# LC_LightCanvas_Rev_1.net
KiCad netlist of a schematic drawn in EAGLE
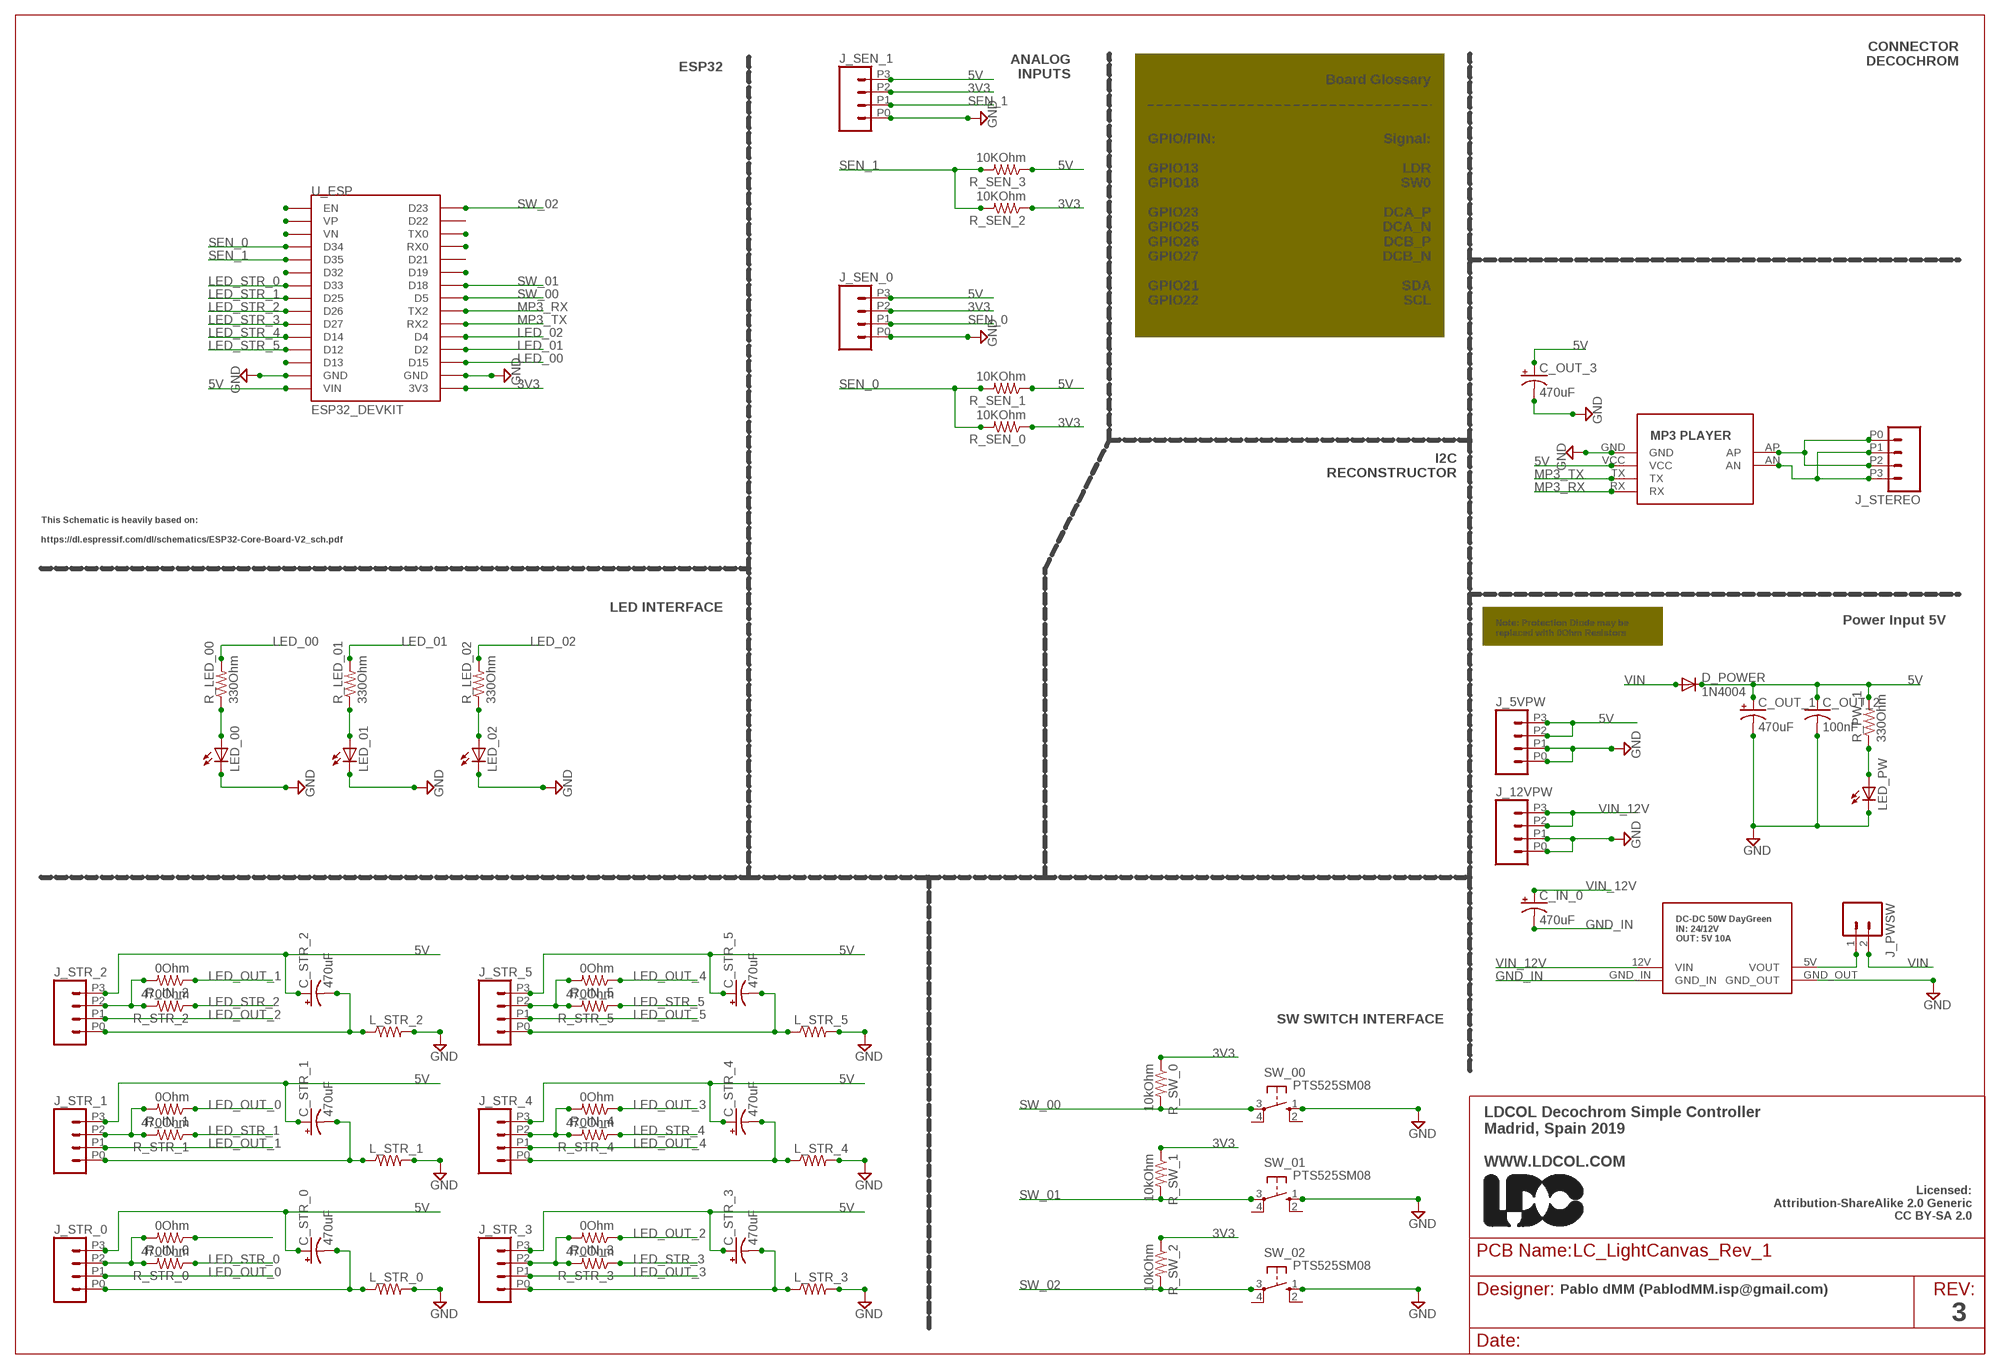
[diagram p0: schematic, sheet 1]

(export (version "E")
  (design (tool "Eeschema 10.0.6"))
  (components
    (comp (ref "C_IN_0")
      (value "470uF")
      (footprint "eagle-import:E5-10,5")
      (libsource (lib "eagle-import") (part "CPOL-USE5-10.5"))
    )
    (comp (ref "C_OUT_1")
      (value "470uF")
      (footprint "eagle-import:E5-10,5")
      (libsource (lib "eagle-import") (part "CPOL-USE5-10.5"))
    )
    (comp (ref "C_OUT_2")
      (value "100nF")
      (footprint "eagle-import:C0805")
      (libsource (lib "eagle-import") (part "C-USC0805"))
    )
    (comp (ref "C_OUT_3")
      (value "470uF")
      (footprint "eagle-import:E5-10,5")
      (libsource (lib "eagle-import") (part "CPOL-USE5-10.5"))
    )
    (comp (ref "C_STR_0")
      (value "470uF")
      (footprint "eagle-import:E5-10,5")
      (libsource (lib "eagle-import") (part "CPOL-USE5-10.5"))
    )
    (comp (ref "C_STR_1")
      (value "470uF")
      (footprint "eagle-import:E5-10,5")
      (libsource (lib "eagle-import") (part "CPOL-USE5-10.5"))
    )
    (comp (ref "C_STR_2")
      (value "470uF")
      (footprint "eagle-import:E5-10,5")
      (libsource (lib "eagle-import") (part "CPOL-USE5-10.5"))
    )
    (comp (ref "C_STR_3")
      (value "470uF")
      (footprint "eagle-import:E5-10,5")
      (libsource (lib "eagle-import") (part "CPOL-USE5-10.5"))
    )
    (comp (ref "C_STR_4")
      (value "470uF")
      (footprint "eagle-import:E5-10,5")
      (libsource (lib "eagle-import") (part "CPOL-USE5-10.5"))
    )
    (comp (ref "C_STR_5")
      (value "470uF")
      (footprint "eagle-import:E5-10,5")
      (libsource (lib "eagle-import") (part "CPOL-USE5-10.5"))
    )
    (comp (ref "D_POWER")
      (value "1N4004")
      (footprint "eagle-import:DO41-10")
      (libsource (lib "eagle-import") (part "1N4004"))
    )
    (comp (ref "J_5VPW")
      (value "M04")
      (footprint "eagle-import:1X04_2.54_SCREWTERM")
      (libsource (lib "eagle-import") (part "M04"))
    )
    (comp (ref "J_12VPW")
      (value "M04")
      (footprint "eagle-import:1X04_2.54_SCREWTERM")
      (libsource (lib "eagle-import") (part "M04"))
    )
    (comp (ref "J_PWSW")
      (value "M023.5MM-NO_SILK")
      (footprint "eagle-import:SCREWTERMINAL-3.5MM-2-NS")
      (libsource (lib "eagle-import") (part "M023.5MM-NO_SILK"))
    )
    (comp (ref "J_SEN_0")
      (value "M04")
      (footprint "eagle-import:1X04_2.54_SCREWTERM")
      (libsource (lib "eagle-import") (part "M04"))
    )
    (comp (ref "J_SEN_1")
      (value "M04")
      (footprint "eagle-import:1X04_2.54_SCREWTERM")
      (libsource (lib "eagle-import") (part "M04"))
    )
    (comp (ref "J_STEREO")
      (value "M04")
      (footprint "eagle-import:1X04_2.54_SCREWTERM")
      (libsource (lib "eagle-import") (part "M04"))
    )
    (comp (ref "J_STR_0")
      (value "M04")
      (footprint "eagle-import:1X04_2.54_SCREWTERM")
      (libsource (lib "eagle-import") (part "M04"))
    )
    (comp (ref "J_STR_1")
      (value "M04")
      (footprint "eagle-import:1X04_2.54_SCREWTERM")
      (libsource (lib "eagle-import") (part "M04"))
    )
    (comp (ref "J_STR_2")
      (value "M04")
      (footprint "eagle-import:1X04_2.54_SCREWTERM")
      (libsource (lib "eagle-import") (part "M04"))
    )
    (comp (ref "J_STR_3")
      (value "M04")
      (footprint "eagle-import:1X04_2.54_SCREWTERM")
      (libsource (lib "eagle-import") (part "M04"))
    )
    (comp (ref "J_STR_4")
      (value "M04")
      (footprint "eagle-import:1X04_2.54_SCREWTERM")
      (libsource (lib "eagle-import") (part "M04"))
    )
    (comp (ref "J_STR_5")
      (value "M04")
      (footprint "eagle-import:1X04_2.54_SCREWTERM")
      (libsource (lib "eagle-import") (part "M04"))
    )
    (comp (ref "LED_00")
      (value "LEDCHIPLED_0805")
      (footprint "eagle-import:CHIPLED_0805")
      (libsource (lib "eagle-import") (part "LEDCHIPLED_0805"))
    )
    (comp (ref "LED_01")
      (value "LEDCHIPLED_0805")
      (footprint "eagle-import:CHIPLED_0805")
      (libsource (lib "eagle-import") (part "LEDCHIPLED_0805"))
    )
    (comp (ref "LED_02")
      (value "LEDCHIPLED_0805")
      (footprint "eagle-import:CHIPLED_0805")
      (libsource (lib "eagle-import") (part "LEDCHIPLED_0805"))
    )
    (comp (ref "LED_PW")
      (value "LEDCHIPLED_0805")
      (footprint "eagle-import:CHIPLED_0805")
      (libsource (lib "eagle-import") (part "LEDCHIPLED_0805"))
    )
    (comp (ref "L_STR_0")
      (value "R-US_R2012")
      (footprint "eagle-import:R2012")
      (libsource (lib "eagle-import") (part "R-US_R2012"))
    )
    (comp (ref "L_STR_1")
      (value "R-US_R2012")
      (footprint "eagle-import:R2012")
      (libsource (lib "eagle-import") (part "R-US_R2012"))
    )
    (comp (ref "L_STR_2")
      (value "R-US_R2012")
      (footprint "eagle-import:R2012")
      (libsource (lib "eagle-import") (part "R-US_R2012"))
    )
    (comp (ref "L_STR_3")
      (value "R-US_R2012")
      (footprint "eagle-import:R2012")
      (libsource (lib "eagle-import") (part "R-US_R2012"))
    )
    (comp (ref "L_STR_4")
      (value "R-US_R2012")
      (footprint "eagle-import:R2012")
      (libsource (lib "eagle-import") (part "R-US_R2012"))
    )
    (comp (ref "L_STR_5")
      (value "R-US_R2012")
      (footprint "eagle-import:R2012")
      (libsource (lib "eagle-import") (part "R-US_R2012"))
    )
    (comp (ref "R_IN_0")
      (value "0Ohm")
      (footprint "eagle-import:M0805")
      (libsource (lib "eagle-import") (part "R-US_M0805"))
    )
    (comp (ref "R_IN_1")
      (value "0Ohm")
      (footprint "eagle-import:M0805")
      (libsource (lib "eagle-import") (part "R-US_M0805"))
    )
    (comp (ref "R_IN_2")
      (value "0Ohm")
      (footprint "eagle-import:M0805")
      (libsource (lib "eagle-import") (part "R-US_M0805"))
    )
    (comp (ref "R_IN_3")
      (value "0Ohm")
      (footprint "eagle-import:M0805")
      (libsource (lib "eagle-import") (part "R-US_M0805"))
    )
    (comp (ref "R_IN_4")
      (value "0Ohm")
      (footprint "eagle-import:M0805")
      (libsource (lib "eagle-import") (part "R-US_M0805"))
    )
    (comp (ref "R_IN_5")
      (value "0Ohm")
      (footprint "eagle-import:M0805")
      (libsource (lib "eagle-import") (part "R-US_M0805"))
    )
    (comp (ref "R_LED_00")
      (value "330Ohm")
      (footprint "eagle-import:M0805")
      (libsource (lib "eagle-import") (part "R-US_M0805"))
    )
    (comp (ref "R_LED_01")
      (value "330Ohm")
      (footprint "eagle-import:M0805")
      (libsource (lib "eagle-import") (part "R-US_M0805"))
    )
    (comp (ref "R_LED_02")
      (value "330Ohm")
      (footprint "eagle-import:M0805")
      (libsource (lib "eagle-import") (part "R-US_M0805"))
    )
    (comp (ref "R_PW_1")
      (value "330Ohm")
      (footprint "eagle-import:M0805")
      (libsource (lib "eagle-import") (part "R-US_M0805"))
    )
    (comp (ref "R_SEN_0")
      (value "10KOhm")
      (footprint "eagle-import:M1206")
      (libsource (lib "eagle-import") (part "R-US_M1206"))
    )
    (comp (ref "R_SEN_1")
      (value "10KOhm")
      (footprint "eagle-import:M1206")
      (libsource (lib "eagle-import") (part "R-US_M1206"))
    )
    (comp (ref "R_SEN_2")
      (value "10KOhm")
      (footprint "eagle-import:M1206")
      (libsource (lib "eagle-import") (part "R-US_M1206"))
    )
    (comp (ref "R_SEN_3")
      (value "10KOhm")
      (footprint "eagle-import:M1206")
      (libsource (lib "eagle-import") (part "R-US_M1206"))
    )
    (comp (ref "R_STR_0")
      (value "470Ohm")
      (footprint "eagle-import:M0805")
      (libsource (lib "eagle-import") (part "R-US_M0805"))
    )
    (comp (ref "R_STR_1")
      (value "470Ohm")
      (footprint "eagle-import:M0805")
      (libsource (lib "eagle-import") (part "R-US_M0805"))
    )
    (comp (ref "R_STR_2")
      (value "470Ohm")
      (footprint "eagle-import:M0805")
      (libsource (lib "eagle-import") (part "R-US_M0805"))
    )
    (comp (ref "R_STR_3")
      (value "470Ohm")
      (footprint "eagle-import:M0805")
      (libsource (lib "eagle-import") (part "R-US_M0805"))
    )
    (comp (ref "R_STR_4")
      (value "470Ohm")
      (footprint "eagle-import:M0805")
      (libsource (lib "eagle-import") (part "R-US_M0805"))
    )
    (comp (ref "R_STR_5")
      (value "470Ohm")
      (footprint "eagle-import:M0805")
      (libsource (lib "eagle-import") (part "R-US_M0805"))
    )
    (comp (ref "R_SW_0")
      (value "10kOhm")
      (footprint "eagle-import:M0805")
      (libsource (lib "eagle-import") (part "R-US_M0805"))
    )
    (comp (ref "R_SW_1")
      (value "10kOhm")
      (footprint "eagle-import:M0805")
      (libsource (lib "eagle-import") (part "R-US_M0805"))
    )
    (comp (ref "R_SW_2")
      (value "10kOhm")
      (footprint "eagle-import:M0805")
      (libsource (lib "eagle-import") (part "R-US_M0805"))
    )
    (comp (ref "SW_00")
      (value "PTS525SM08")
      (footprint "eagle-import:SM08")
      (fields (field (name "MF") "C&K Components") (field (name "MPN") "PTS525SM08SMTR2LFS"))
      (libsource (lib "eagle-import") (part "PTS52508SM"))
    )
    (comp (ref "SW_01")
      (value "PTS525SM08")
      (footprint "eagle-import:SM08")
      (fields (field (name "MF") "C&K Components") (field (name "MPN") "PTS525SM08SMTR2LFS"))
      (libsource (lib "eagle-import") (part "PTS52508SM"))
    )
    (comp (ref "SW_02")
      (value "PTS525SM08")
      (footprint "eagle-import:SM08")
      (fields (field (name "MF") "C&K Components") (field (name "MPN") "PTS525SM08SMTR2LFS"))
      (libsource (lib "eagle-import") (part "PTS52508SM"))
    )
    (comp (ref "U$1")
      (value "DC_CONVERTER")
      (footprint "eagle-import:DC_CONVERTER")
      (libsource (lib "eagle-import") (part "DC_CONVERTER"))
    )
    (comp (ref "U$2")
      (value "MP3_PLAYER")
      (footprint "eagle-import:MP3_PLAYER")
      (libsource (lib "eagle-import") (part "MP3_PLAYER"))
    )
    (comp (ref "U_ESP")
      (value "ESP32_DEVKIT")
      (footprint "eagle-import:ESP32_DEVKIT")
      (libsource (lib "eagle-import") (part "ESP32_DEVKIT"))
    )
  )
  (nets
    (net (code "1") (name "/3V3") (class "Default")
      (node (ref "J_SEN_0") (pin "P2") (pinfunction "3_P2") (pintype "passive"))
      (node (ref "J_SEN_1") (pin "P2") (pinfunction "3_P2") (pintype "passive"))
      (node (ref "R_SEN_0") (pin "1") (pinfunction "1_1") (pintype "passive"))
      (node (ref "R_SEN_2") (pin "1") (pinfunction "1_1") (pintype "passive"))
      (node (ref "R_SW_0") (pin "1") (pinfunction "1_1") (pintype "passive"))
      (node (ref "R_SW_1") (pin "1") (pinfunction "1_1") (pintype "passive"))
      (node (ref "R_SW_2") (pin "1") (pinfunction "1_1") (pintype "passive"))
      (node (ref "U_ESP") (pin "3V3") (pinfunction "3V3_3V3") (pintype "bidirectional"))
    )
    (net (code "2") (name "/5V") (class "Default")
      (node (ref "C_OUT_1") (pin "+") (pinfunction "+_+") (pintype "passive"))
      (node (ref "C_OUT_2") (pin "1") (pinfunction "1_1") (pintype "passive"))
      (node (ref "C_OUT_3") (pin "+") (pinfunction "+_+") (pintype "passive"))
      (node (ref "C_STR_0") (pin "+") (pinfunction "+_+") (pintype "passive"))
      (node (ref "C_STR_1") (pin "+") (pinfunction "+_+") (pintype "passive"))
      (node (ref "C_STR_2") (pin "+") (pinfunction "+_+") (pintype "passive"))
      (node (ref "C_STR_3") (pin "+") (pinfunction "+_+") (pintype "passive"))
      (node (ref "C_STR_4") (pin "+") (pinfunction "+_+") (pintype "passive"))
      (node (ref "C_STR_5") (pin "+") (pinfunction "+_+") (pintype "passive"))
      (node (ref "D_POWER") (pin "C") (pinfunction "C_C") (pintype "passive"))
      (node (ref "J_5VPW") (pin "P2") (pinfunction "3_P2") (pintype "passive"))
      (node (ref "J_5VPW") (pin "P3") (pinfunction "4_P3") (pintype "passive"))
      (node (ref "J_SEN_0") (pin "P3") (pinfunction "4_P3") (pintype "passive"))
      (node (ref "J_SEN_1") (pin "P3") (pinfunction "4_P3") (pintype "passive"))
      (node (ref "J_STR_0") (pin "P3") (pinfunction "4_P3") (pintype "passive"))
      (node (ref "J_STR_1") (pin "P3") (pinfunction "4_P3") (pintype "passive"))
      (node (ref "J_STR_2") (pin "P3") (pinfunction "4_P3") (pintype "passive"))
      (node (ref "J_STR_3") (pin "P3") (pinfunction "4_P3") (pintype "passive"))
      (node (ref "J_STR_4") (pin "P3") (pinfunction "4_P3") (pintype "passive"))
      (node (ref "J_STR_5") (pin "P3") (pinfunction "4_P3") (pintype "passive"))
      (node (ref "R_PW_1") (pin "2") (pinfunction "2_2") (pintype "passive"))
      (node (ref "R_SEN_1") (pin "1") (pinfunction "1_1") (pintype "passive"))
      (node (ref "R_SEN_3") (pin "1") (pinfunction "1_1") (pintype "passive"))
      (node (ref "U$2") (pin "VCC") (pinfunction "VCC_VCC") (pintype "bidirectional"))
      (node (ref "U_ESP") (pin "VIN") (pinfunction "VIN_VIN") (pintype "bidirectional"))
    )
    (net (code "3") (name "/GND_IN") (class "Default")
      (node (ref "C_IN_0") (pin "-") (pinfunction "-_-") (pintype "passive"))
      (node (ref "U$1") (pin "GND_IN") (pinfunction "GND_IN_GND_IN") (pintype "bidirectional"))
    )
    (net (code "4") (name "/LED_00") (class "Default")
      (node (ref "R_LED_00") (pin "2") (pinfunction "2_2") (pintype "passive"))
      (node (ref "U_ESP") (pin "D15") (pinfunction "D15_D15") (pintype "bidirectional"))
    )
    (net (code "5") (name "/LED_01") (class "Default")
      (node (ref "R_LED_01") (pin "2") (pinfunction "2_2") (pintype "passive"))
      (node (ref "U_ESP") (pin "D2") (pinfunction "D2_D2") (pintype "bidirectional"))
    )
    (net (code "6") (name "/LED_02") (class "Default")
      (node (ref "R_LED_02") (pin "2") (pinfunction "2_2") (pintype "passive"))
      (node (ref "U_ESP") (pin "D4") (pinfunction "D4_D4") (pintype "bidirectional"))
    )
    (net (code "7") (name "/LED_OUT_0") (class "Default")
      (node (ref "J_STR_0") (pin "P1") (pinfunction "2_P1") (pintype "passive"))
      (node (ref "R_IN_1") (pin "1") (pinfunction "1_1") (pintype "passive"))
    )
    (net (code "8") (name "/LED_OUT_1") (class "Default")
      (node (ref "J_STR_1") (pin "P1") (pinfunction "2_P1") (pintype "passive"))
      (node (ref "R_IN_2") (pin "1") (pinfunction "1_1") (pintype "passive"))
    )
    (net (code "9") (name "/LED_OUT_2") (class "Default")
      (node (ref "J_STR_2") (pin "P1") (pinfunction "2_P1") (pintype "passive"))
      (node (ref "R_IN_3") (pin "1") (pinfunction "1_1") (pintype "passive"))
    )
    (net (code "10") (name "/LED_OUT_3") (class "Default")
      (node (ref "J_STR_3") (pin "P1") (pinfunction "2_P1") (pintype "passive"))
      (node (ref "R_IN_4") (pin "1") (pinfunction "1_1") (pintype "passive"))
    )
    (net (code "11") (name "/LED_OUT_4") (class "Default")
      (node (ref "J_STR_4") (pin "P1") (pinfunction "2_P1") (pintype "passive"))
      (node (ref "R_IN_5") (pin "1") (pinfunction "1_1") (pintype "passive"))
    )
    (net (code "12") (name "/LED_OUT_5") (class "Default")
      (node (ref "J_STR_5") (pin "P1") (pinfunction "2_P1") (pintype "passive"))
    )
    (net (code "13") (name "/LED_STR_0") (class "Default")
      (node (ref "R_STR_0") (pin "1") (pinfunction "1_1") (pintype "passive"))
      (node (ref "U_ESP") (pin "D33") (pinfunction "D33_D33") (pintype "bidirectional"))
    )
    (net (code "14") (name "/LED_STR_1") (class "Default")
      (node (ref "R_STR_1") (pin "1") (pinfunction "1_1") (pintype "passive"))
      (node (ref "U_ESP") (pin "D25") (pinfunction "D25_D25") (pintype "bidirectional"))
    )
    (net (code "15") (name "/LED_STR_2") (class "Default")
      (node (ref "R_STR_2") (pin "1") (pinfunction "1_1") (pintype "passive"))
      (node (ref "U_ESP") (pin "D26") (pinfunction "D26_D26") (pintype "bidirectional"))
    )
    (net (code "16") (name "/LED_STR_3") (class "Default")
      (node (ref "R_STR_3") (pin "1") (pinfunction "1_1") (pintype "passive"))
      (node (ref "U_ESP") (pin "D27") (pinfunction "D27_D27") (pintype "bidirectional"))
    )
    (net (code "17") (name "/LED_STR_4") (class "Default")
      (node (ref "R_STR_4") (pin "1") (pinfunction "1_1") (pintype "passive"))
      (node (ref "U_ESP") (pin "D14") (pinfunction "D14_D14") (pintype "bidirectional"))
    )
    (net (code "18") (name "/LED_STR_5") (class "Default")
      (node (ref "R_STR_5") (pin "1") (pinfunction "1_1") (pintype "passive"))
      (node (ref "U_ESP") (pin "D12") (pinfunction "D12_D12") (pintype "bidirectional"))
    )
    (net (code "19") (name "/MP3_RX") (class "Default")
      (node (ref "U$2") (pin "RX") (pinfunction "RX_RX") (pintype "bidirectional"))
      (node (ref "U_ESP") (pin "TX2") (pinfunction "TX2_TX2") (pintype "bidirectional"))
    )
    (net (code "20") (name "/MP3_TX") (class "Default")
      (node (ref "U$2") (pin "TX") (pinfunction "TX_TX") (pintype "bidirectional"))
      (node (ref "U_ESP") (pin "RX2") (pinfunction "RX2_RX2") (pintype "bidirectional"))
    )
    (net (code "21") (name "/SEN_0") (class "Default")
      (node (ref "J_SEN_0") (pin "P1") (pinfunction "2_P1") (pintype "passive"))
      (node (ref "R_SEN_0") (pin "2") (pinfunction "2_2") (pintype "passive"))
      (node (ref "R_SEN_1") (pin "2") (pinfunction "2_2") (pintype "passive"))
      (node (ref "U_ESP") (pin "D34") (pinfunction "D34_D34") (pintype "bidirectional"))
    )
    (net (code "22") (name "/SEN_1") (class "Default")
      (node (ref "J_SEN_1") (pin "P1") (pinfunction "2_P1") (pintype "passive"))
      (node (ref "R_SEN_2") (pin "2") (pinfunction "2_2") (pintype "passive"))
      (node (ref "R_SEN_3") (pin "2") (pinfunction "2_2") (pintype "passive"))
      (node (ref "U_ESP") (pin "D35") (pinfunction "D35_D35") (pintype "bidirectional"))
    )
    (net (code "23") (name "/SW_00") (class "Default")
      (node (ref "R_SW_0") (pin "2") (pinfunction "2_2") (pintype "passive"))
      (node (ref "SW_00") (pin "3") (pinfunction "P_3") (pintype "passive"))
      (node (ref "U_ESP") (pin "D5") (pinfunction "D5_D5") (pintype "bidirectional"))
    )
    (net (code "24") (name "/SW_01") (class "Default")
      (node (ref "R_SW_1") (pin "2") (pinfunction "2_2") (pintype "passive"))
      (node (ref "SW_01") (pin "3") (pinfunction "P_3") (pintype "passive"))
      (node (ref "U_ESP") (pin "D18") (pinfunction "D18_D18") (pintype "bidirectional"))
    )
    (net (code "25") (name "/SW_02") (class "Default")
      (node (ref "R_SW_2") (pin "2") (pinfunction "2_2") (pintype "passive"))
      (node (ref "SW_02") (pin "3") (pinfunction "P_3") (pintype "passive"))
      (node (ref "U_ESP") (pin "D23") (pinfunction "D23_D23") (pintype "bidirectional"))
    )
    (net (code "26") (name "/VIN") (class "Default")
      (node (ref "D_POWER") (pin "A") (pinfunction "A_A") (pintype "passive"))
      (node (ref "J_PWSW") (pin "2") (pinfunction "2_2") (pintype "passive"))
    )
    (net (code "27") (name "/VIN_12V") (class "Default")
      (node (ref "C_IN_0") (pin "+") (pinfunction "+_+") (pintype "passive"))
      (node (ref "J_12VPW") (pin "P2") (pinfunction "3_P2") (pintype "passive"))
      (node (ref "J_12VPW") (pin "P3") (pinfunction "4_P3") (pintype "passive"))
      (node (ref "U$1") (pin "12V") (pinfunction "VIN_12V") (pintype "bidirectional"))
    )
    (net (code "28") (name "GND") (class "Default")
      (node (ref "C_OUT_1") (pin "-") (pinfunction "-_-") (pintype "passive"))
      (node (ref "C_OUT_2") (pin "2") (pinfunction "2_2") (pintype "passive"))
      (node (ref "C_OUT_3") (pin "-") (pinfunction "-_-") (pintype "passive"))
      (node (ref "J_12VPW") (pin "P0") (pinfunction "1_P0") (pintype "passive"))
      (node (ref "J_12VPW") (pin "P1") (pinfunction "2_P1") (pintype "passive"))
      (node (ref "J_5VPW") (pin "P0") (pinfunction "1_P0") (pintype "passive"))
      (node (ref "J_5VPW") (pin "P1") (pinfunction "2_P1") (pintype "passive"))
      (node (ref "J_SEN_0") (pin "P0") (pinfunction "1_P0") (pintype "passive"))
      (node (ref "J_SEN_1") (pin "P0") (pinfunction "1_P0") (pintype "passive"))
      (node (ref "LED_00") (pin "C") (pinfunction "C_C") (pintype "passive"))
      (node (ref "LED_01") (pin "C") (pinfunction "C_C") (pintype "passive"))
      (node (ref "LED_02") (pin "C") (pinfunction "C_C") (pintype "passive"))
      (node (ref "LED_PW") (pin "C") (pinfunction "C_C") (pintype "passive"))
      (node (ref "L_STR_0") (pin "2") (pinfunction "2_2") (pintype "passive"))
      (node (ref "L_STR_1") (pin "2") (pinfunction "2_2") (pintype "passive"))
      (node (ref "L_STR_2") (pin "2") (pinfunction "2_2") (pintype "passive"))
      (node (ref "L_STR_3") (pin "2") (pinfunction "2_2") (pintype "passive"))
      (node (ref "L_STR_4") (pin "2") (pinfunction "2_2") (pintype "passive"))
      (node (ref "L_STR_5") (pin "2") (pinfunction "2_2") (pintype "passive"))
      (node (ref "SW_00") (pin "1") (pinfunction "S_1") (pintype "passive"))
      (node (ref "SW_01") (pin "1") (pinfunction "S_1") (pintype "passive"))
      (node (ref "SW_02") (pin "1") (pinfunction "S_1") (pintype "passive"))
      (node (ref "U$1") (pin "GND_OUT") (pinfunction "GND_OUT_GND_OUT") (pintype "bidirectional"))
      (node (ref "U$2") (pin "GND") (pinfunction "GND_GND") (pintype "bidirectional"))
      (node (ref "U_ESP") (pin "GND@1") (pinfunction "GND_GND@1") (pintype "bidirectional"))
      (node (ref "U_ESP") (pin "GND@2") (pinfunction "GND_GND@2") (pintype "bidirectional"))
    )
    (net (code "29") (name "Net-(J_STEREO-1)") (class "Default")
      (node (ref "J_STEREO") (pin "P0") (pinfunction "1_P0") (pintype "passive"))
      (node (ref "J_STEREO") (pin "P2") (pinfunction "3_P2") (pintype "passive"))
      (node (ref "U$2") (pin "AP") (pinfunction "AP_AP") (pintype "bidirectional"))
    )
    (net (code "30") (name "Net-(J_STEREO-2)") (class "Default")
      (node (ref "J_STEREO") (pin "P1") (pinfunction "2_P1") (pintype "passive"))
      (node (ref "J_STEREO") (pin "P3") (pinfunction "4_P3") (pintype "passive"))
      (node (ref "U$2") (pin "AN") (pinfunction "AN_AN") (pintype "bidirectional"))
    )
    (net (code "31") (name "Net-(J_STR_0-1)") (class "Default")
      (node (ref "C_STR_0") (pin "-") (pinfunction "-_-") (pintype "passive"))
      (node (ref "J_STR_0") (pin "P0") (pinfunction "1_P0") (pintype "passive"))
      (node (ref "L_STR_0") (pin "1") (pinfunction "1_1") (pintype "passive"))
    )
    (net (code "32") (name "Net-(J_STR_0-3)") (class "Default")
      (node (ref "J_STR_0") (pin "P2") (pinfunction "3_P2") (pintype "passive"))
      (node (ref "R_IN_0") (pin "2") (pinfunction "2_2") (pintype "passive"))
      (node (ref "R_STR_0") (pin "2") (pinfunction "2_2") (pintype "passive"))
    )
    (net (code "33") (name "Net-(J_STR_1-1)") (class "Default")
      (node (ref "C_STR_1") (pin "-") (pinfunction "-_-") (pintype "passive"))
      (node (ref "J_STR_1") (pin "P0") (pinfunction "1_P0") (pintype "passive"))
      (node (ref "L_STR_1") (pin "1") (pinfunction "1_1") (pintype "passive"))
    )
    (net (code "34") (name "Net-(J_STR_1-3)") (class "Default")
      (node (ref "J_STR_1") (pin "P2") (pinfunction "3_P2") (pintype "passive"))
      (node (ref "R_IN_1") (pin "2") (pinfunction "2_2") (pintype "passive"))
      (node (ref "R_STR_1") (pin "2") (pinfunction "2_2") (pintype "passive"))
    )
    (net (code "35") (name "Net-(J_STR_2-1)") (class "Default")
      (node (ref "C_STR_2") (pin "-") (pinfunction "-_-") (pintype "passive"))
      (node (ref "J_STR_2") (pin "P0") (pinfunction "1_P0") (pintype "passive"))
      (node (ref "L_STR_2") (pin "1") (pinfunction "1_1") (pintype "passive"))
    )
    (net (code "36") (name "Net-(J_STR_2-3)") (class "Default")
      (node (ref "J_STR_2") (pin "P2") (pinfunction "3_P2") (pintype "passive"))
      (node (ref "R_IN_2") (pin "2") (pinfunction "2_2") (pintype "passive"))
      (node (ref "R_STR_2") (pin "2") (pinfunction "2_2") (pintype "passive"))
    )
    (net (code "37") (name "Net-(J_STR_3-1)") (class "Default")
      (node (ref "C_STR_3") (pin "-") (pinfunction "-_-") (pintype "passive"))
      (node (ref "J_STR_3") (pin "P0") (pinfunction "1_P0") (pintype "passive"))
      (node (ref "L_STR_3") (pin "1") (pinfunction "1_1") (pintype "passive"))
    )
    (net (code "38") (name "Net-(J_STR_3-3)") (class "Default")
      (node (ref "J_STR_3") (pin "P2") (pinfunction "3_P2") (pintype "passive"))
      (node (ref "R_IN_3") (pin "2") (pinfunction "2_2") (pintype "passive"))
      (node (ref "R_STR_3") (pin "2") (pinfunction "2_2") (pintype "passive"))
    )
    (net (code "39") (name "Net-(J_STR_4-1)") (class "Default")
      (node (ref "C_STR_4") (pin "-") (pinfunction "-_-") (pintype "passive"))
      (node (ref "J_STR_4") (pin "P0") (pinfunction "1_P0") (pintype "passive"))
      (node (ref "L_STR_4") (pin "1") (pinfunction "1_1") (pintype "passive"))
    )
    (net (code "40") (name "Net-(J_STR_4-3)") (class "Default")
      (node (ref "J_STR_4") (pin "P2") (pinfunction "3_P2") (pintype "passive"))
      (node (ref "R_IN_4") (pin "2") (pinfunction "2_2") (pintype "passive"))
      (node (ref "R_STR_4") (pin "2") (pinfunction "2_2") (pintype "passive"))
    )
    (net (code "41") (name "Net-(J_STR_5-1)") (class "Default")
      (node (ref "C_STR_5") (pin "-") (pinfunction "-_-") (pintype "passive"))
      (node (ref "J_STR_5") (pin "P0") (pinfunction "1_P0") (pintype "passive"))
      (node (ref "L_STR_5") (pin "1") (pinfunction "1_1") (pintype "passive"))
    )
    (net (code "42") (name "Net-(J_STR_5-3)") (class "Default")
      (node (ref "J_STR_5") (pin "P2") (pinfunction "3_P2") (pintype "passive"))
      (node (ref "R_IN_5") (pin "2") (pinfunction "2_2") (pintype "passive"))
      (node (ref "R_STR_5") (pin "2") (pinfunction "2_2") (pintype "passive"))
    )
    (net (code "43") (name "Net-(LED_00-PadA)") (class "Default")
      (node (ref "LED_00") (pin "A") (pinfunction "A_A") (pintype "passive"))
      (node (ref "R_LED_00") (pin "1") (pinfunction "1_1") (pintype "passive"))
    )
    (net (code "44") (name "Net-(LED_01-PadA)") (class "Default")
      (node (ref "LED_01") (pin "A") (pinfunction "A_A") (pintype "passive"))
      (node (ref "R_LED_01") (pin "1") (pinfunction "1_1") (pintype "passive"))
    )
    (net (code "45") (name "Net-(LED_02-PadA)") (class "Default")
      (node (ref "LED_02") (pin "A") (pinfunction "A_A") (pintype "passive"))
      (node (ref "R_LED_02") (pin "1") (pinfunction "1_1") (pintype "passive"))
    )
    (net (code "46") (name "Net-(LED_PW-PadA)") (class "Default")
      (node (ref "LED_PW") (pin "A") (pinfunction "A_A") (pintype "passive"))
      (node (ref "R_PW_1") (pin "1") (pinfunction "1_1") (pintype "passive"))
    )
    (net (code "47") (name "Net-(U$1-VOUT)") (class "Default")
      (node (ref "J_PWSW") (pin "1") (pinfunction "1_1") (pintype "passive"))
      (node (ref "U$1") (pin "5V") (pinfunction "VOUT_5V") (pintype "bidirectional"))
    )
    (net (code "48") (name "unconnected-(R_IN_0-Pad1)") (class "Default")
      (node (ref "R_IN_0") (pin "1") (pinfunction "1_1") (pintype "passive"))
    )
    (net (code "49") (name "unconnected-(SW_00-P-Pad4)") (class "Default")
      (node (ref "SW_00") (pin "4") (pinfunction "P_4") (pintype "passive"))
    )
    (net (code "50") (name "unconnected-(SW_00-S-Pad2)") (class "Default")
      (node (ref "SW_00") (pin "2") (pinfunction "S_2") (pintype "passive"))
    )
    (net (code "51") (name "unconnected-(SW_01-P-Pad4)") (class "Default")
      (node (ref "SW_01") (pin "4") (pinfunction "P_4") (pintype "passive"))
    )
    (net (code "52") (name "unconnected-(SW_01-S-Pad2)") (class "Default")
      (node (ref "SW_01") (pin "2") (pinfunction "S_2") (pintype "passive"))
    )
    (net (code "53") (name "unconnected-(SW_02-P-Pad4)") (class "Default")
      (node (ref "SW_02") (pin "4") (pinfunction "P_4") (pintype "passive"))
    )
    (net (code "54") (name "unconnected-(SW_02-S-Pad2)") (class "Default")
      (node (ref "SW_02") (pin "2") (pinfunction "S_2") (pintype "passive"))
    )
    (net (code "55") (name "unconnected-(U_ESP-PadD13)") (class "Default")
      (node (ref "U_ESP") (pin "D13") (pinfunction "D13_D13") (pintype "bidirectional"))
    )
    (net (code "56") (name "unconnected-(U_ESP-PadD19)") (class "Default")
      (node (ref "U_ESP") (pin "D19") (pinfunction "D19_D19") (pintype "bidirectional"))
    )
    (net (code "57") (name "unconnected-(U_ESP-PadD21)") (class "Default")
      (node (ref "U_ESP") (pin "D21") (pinfunction "D21_D21") (pintype "bidirectional"))
    )
    (net (code "58") (name "unconnected-(U_ESP-PadD22)") (class "Default")
      (node (ref "U_ESP") (pin "D22") (pinfunction "D22_D22") (pintype "bidirectional"))
    )
    (net (code "59") (name "unconnected-(U_ESP-PadD32)") (class "Default")
      (node (ref "U_ESP") (pin "D32") (pinfunction "D32_D32") (pintype "bidirectional"))
    )
    (net (code "60") (name "unconnected-(U_ESP-PadEN)") (class "Default")
      (node (ref "U_ESP") (pin "EN") (pinfunction "EN_EN") (pintype "bidirectional"))
    )
    (net (code "61") (name "unconnected-(U_ESP-PadRX0)") (class "Default")
      (node (ref "U_ESP") (pin "RX0") (pinfunction "RX0_RX0") (pintype "bidirectional"))
    )
    (net (code "62") (name "unconnected-(U_ESP-PadTX0)") (class "Default")
      (node (ref "U_ESP") (pin "TX0") (pinfunction "TX0_TX0") (pintype "bidirectional"))
    )
    (net (code "63") (name "unconnected-(U_ESP-PadVN)") (class "Default")
      (node (ref "U_ESP") (pin "VN") (pinfunction "VN_VN") (pintype "bidirectional"))
    )
    (net (code "64") (name "unconnected-(U_ESP-PadVP)") (class "Default")
      (node (ref "U_ESP") (pin "VP") (pinfunction "VP_VP") (pintype "bidirectional"))
    )
  )
)
